# processor_board.net
KiCad netlist of a schematic drawn in EAGLE
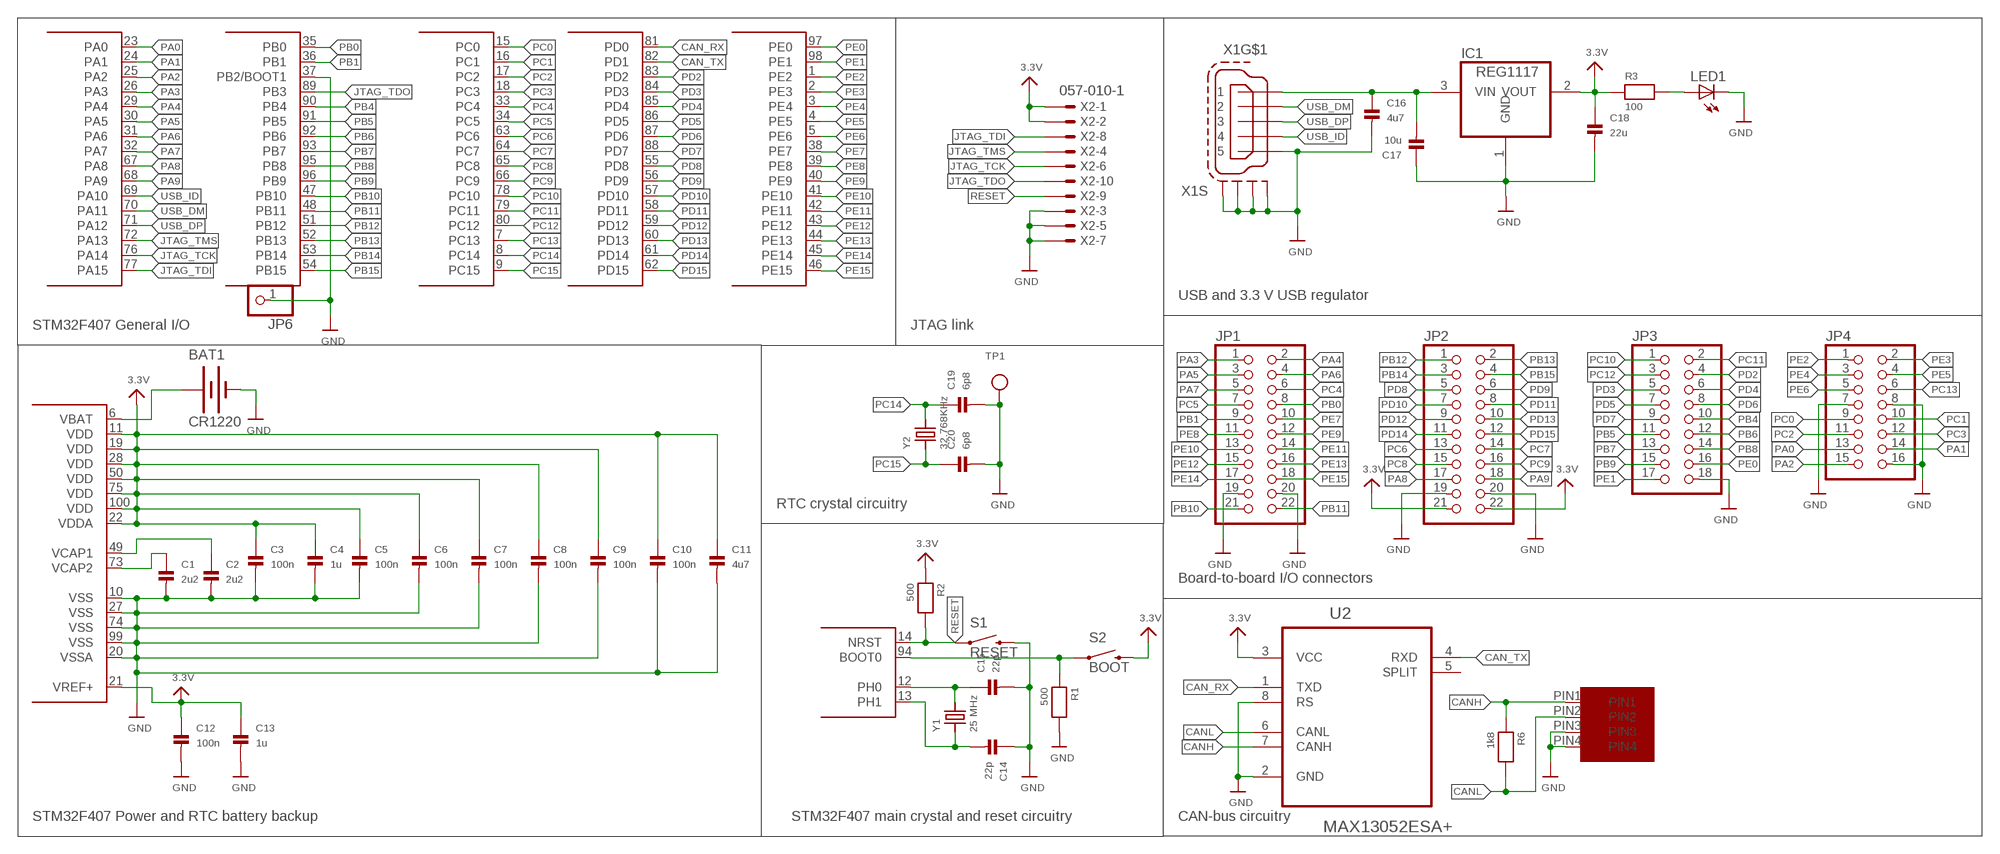
[diagram p0: schematic, sheet 1]

(export (version "E")
  (design (tool "Eeschema 10.0.6"))
  (components
    (comp (ref "BAT1")
      (value "CR1220")
      (footprint "eagle-import:BATTCON_12MM_PTH")
      (libsource (lib "eagle-import") (part "BATTERY12PTH"))
    )
    (comp (ref "C1")
      (value "2u2")
      (footprint "eagle-import:_0603MP")
      (libsource (lib "eagle-import") (part "CAP_CERAMIC_0603MP"))
    )
    (comp (ref "C2")
      (value "2u2")
      (footprint "eagle-import:_0603MP")
      (libsource (lib "eagle-import") (part "CAP_CERAMIC_0603MP"))
    )
    (comp (ref "C3")
      (value "100n")
      (footprint "eagle-import:_0603MP")
      (libsource (lib "eagle-import") (part "CAP_CERAMIC_0603MP"))
    )
    (comp (ref "C4")
      (value "1u")
      (footprint "eagle-import:_0603MP")
      (libsource (lib "eagle-import") (part "CAP_CERAMIC_0603MP"))
    )
    (comp (ref "C5")
      (value "100n")
      (footprint "eagle-import:_0603MP")
      (libsource (lib "eagle-import") (part "CAP_CERAMIC_0603MP"))
    )
    (comp (ref "C6")
      (value "100n")
      (footprint "eagle-import:_0603MP")
      (libsource (lib "eagle-import") (part "CAP_CERAMIC_0603MP"))
    )
    (comp (ref "C7")
      (value "100n")
      (footprint "eagle-import:_0603MP")
      (libsource (lib "eagle-import") (part "CAP_CERAMIC_0603MP"))
    )
    (comp (ref "C8")
      (value "100n")
      (footprint "eagle-import:_0603MP")
      (libsource (lib "eagle-import") (part "CAP_CERAMIC_0603MP"))
    )
    (comp (ref "C9")
      (value "100n")
      (footprint "eagle-import:_0603MP")
      (libsource (lib "eagle-import") (part "CAP_CERAMIC_0603MP"))
    )
    (comp (ref "C10")
      (value "100n")
      (footprint "eagle-import:_0603MP")
      (libsource (lib "eagle-import") (part "CAP_CERAMIC_0603MP"))
    )
    (comp (ref "C11")
      (value "4u7")
      (footprint "eagle-import:_0603MP")
      (libsource (lib "eagle-import") (part "CAP_CERAMIC_0603MP"))
    )
    (comp (ref "C12")
      (value "100n")
      (footprint "eagle-import:_0603MP")
      (libsource (lib "eagle-import") (part "CAP_CERAMIC_0603MP"))
    )
    (comp (ref "C13")
      (value "1u")
      (footprint "eagle-import:_0603MP")
      (libsource (lib "eagle-import") (part "CAP_CERAMIC_0603MP"))
    )
    (comp (ref "C14")
      (value "22p")
      (footprint "eagle-import:_0603MP")
      (libsource (lib "eagle-import") (part "CAP_CERAMIC_0603MP"))
    )
    (comp (ref "C15")
      (value "22p")
      (footprint "eagle-import:_0603MP")
      (libsource (lib "eagle-import") (part "CAP_CERAMIC_0603MP"))
    )
    (comp (ref "C16")
      (value "4u7")
      (footprint "eagle-import:_0603MP")
      (libsource (lib "eagle-import") (part "CAP_CERAMIC_0603MP"))
    )
    (comp (ref "C17")
      (value "10u")
      (footprint "eagle-import:_0603MP")
      (libsource (lib "eagle-import") (part "CAP_CERAMIC_0603MP"))
    )
    (comp (ref "C18")
      (value "22u")
      (footprint "eagle-import:_0603MP")
      (libsource (lib "eagle-import") (part "CAP_CERAMIC_0603MP"))
    )
    (comp (ref "C19")
      (value "6p8")
      (footprint "eagle-import:_0603MP")
      (libsource (lib "eagle-import") (part "CAP_CERAMIC_0603MP"))
    )
    (comp (ref "C20")
      (value "6p8")
      (footprint "eagle-import:_0603MP")
      (libsource (lib "eagle-import") (part "CAP_CERAMIC_0603MP"))
    )
    (comp (ref "IC1")
      (value "REG1117")
      (footprint "eagle-import:SOT223")
      (libsource (lib "eagle-import") (part "REG1117"))
    )
    (comp (ref "JP1")
      (value "PINHD-2X11")
      (footprint "eagle-import:2X11")
      (libsource (lib "eagle-import") (part "PINHD-2X11"))
    )
    (comp (ref "JP2")
      (value "PINHD-2X11")
      (footprint "eagle-import:2X11")
      (libsource (lib "eagle-import") (part "PINHD-2X11"))
    )
    (comp (ref "JP3")
      (value "PINHD-2X9")
      (footprint "eagle-import:2X09")
      (libsource (lib "eagle-import") (part "PINHD-2X9"))
    )
    (comp (ref "JP4")
      (value "PINHD-2X8")
      (footprint "eagle-import:2X08")
      (libsource (lib "eagle-import") (part "PINHD-2X8"))
    )
    (comp (ref "JP6")
      (value "PINHD-1X1")
      (footprint "eagle-import:1X01")
      (libsource (lib "eagle-import") (part "PINHD-1X1"))
    )
    (comp (ref "LED1")
      (value "LEDCHIPLED_1206")
      (footprint "eagle-import:CHIPLED_1206")
      (libsource (lib "eagle-import") (part "LEDCHIPLED_1206"))
    )
    (comp (ref "R1")
      (value "500")
      (footprint "eagle-import:_0603MP")
      (libsource (lib "eagle-import") (part "RESISTOR_0603MP"))
    )
    (comp (ref "R2")
      (value "500")
      (footprint "eagle-import:_0603MP")
      (libsource (lib "eagle-import") (part "RESISTOR_0603MP"))
    )
    (comp (ref "R3")
      (value "100")
      (footprint "eagle-import:_0603MP")
      (libsource (lib "eagle-import") (part "RESISTOR_0603MP"))
    )
    (comp (ref "R6")
      (value "1k8")
      (footprint "eagle-import:_0603MP")
      (libsource (lib "eagle-import") (part "RESISTOR_0603MP"))
    )
    (comp (ref "S1")
      (value "RESET")
      (footprint "eagle-import:TACTILE-SWITCH-1101NE")
      (libsource (lib "eagle-import") (part "SWITCH-MOMENTARY-2SMD-1101NE"))
    )
    (comp (ref "S2")
      (value "BOOT")
      (footprint "eagle-import:TACTILE-SWITCH-1101NE")
      (libsource (lib "eagle-import") (part "SWITCH-MOMENTARY-2SMD-1101NE"))
    )
    (comp (ref "TP1")
      (value "TESTPOINT0.1\"")
      (footprint "eagle-import:1X01_ROUND")
      (libsource (lib "eagle-import") (part "TESTPOINT0.1{dblquote}"))
    )
    (comp (ref "U$23")
      (value "MICROFIT4")
      (footprint "eagle-import:MICROFIT4SOCK")
      (libsource (lib "eagle-import") (part "MICROFIT4"))
    )
    (comp (ref "U1")
      (value "STM32F4-100")
      (footprint "eagle-import:SQFP-S-14X14-100")
      (libsource (lib "eagle-import") (part "STM32F4-100"))
    )
    (comp (ref "U2")
      (value "MAX13052ESA+")
      (footprint "eagle-import:SOIC127P600X175-8N")
      (libsource (lib "eagle-import") (part "MAX13052ESA+"))
    )
    (comp (ref "X1")
      (value "MINI-USB-SCHIELD-32005-201")
      (footprint "eagle-import:32005-201")
      (libsource (lib "eagle-import") (part "MINI-USB-SCHIELD-32005-201"))
    )
    (comp (ref "X2")
      (value "057-010-1")
      (footprint "eagle-import:057-010-1")
      (libsource (lib "eagle-import") (part "057-010-1"))
    )
    (comp (ref "Y1")
      (value "25 MHz")
      (footprint "eagle-import:CRYSTAL_2.5X2")
      (libsource (lib "eagle-import") (part "CRYSTAL2.5X2.0MM"))
    )
    (comp (ref "Y2")
      (value "32.768KHz")
      (footprint "eagle-import:CRYSTAL_CYL_2X6MM_SMT")
      (libsource (lib "eagle-import") (part "CRYSTAL32.768"))
    )
  )
  (nets
    (net (code "1") (name "3.3V") (class "Default")
      (node (ref "C10") (pin "1") (pinfunction "P$1_1") (pintype "passive"))
      (node (ref "C11") (pin "1") (pinfunction "P$1_1") (pintype "passive"))
      (node (ref "C12") (pin "1") (pinfunction "P$1_1") (pintype "passive"))
      (node (ref "C13") (pin "1") (pinfunction "P$1_1") (pintype "passive"))
      (node (ref "C18") (pin "1") (pinfunction "P$1_1") (pintype "passive"))
      (node (ref "C3") (pin "1") (pinfunction "P$1_1") (pintype "passive"))
      (node (ref "C4") (pin "1") (pinfunction "P$1_1") (pintype "passive"))
      (node (ref "C5") (pin "1") (pinfunction "P$1_1") (pintype "passive"))
      (node (ref "C6") (pin "1") (pinfunction "P$1_1") (pintype "passive"))
      (node (ref "C7") (pin "1") (pinfunction "P$1_1") (pintype "passive"))
      (node (ref "C8") (pin "1") (pinfunction "P$1_1") (pintype "passive"))
      (node (ref "C9") (pin "1") (pinfunction "P$1_1") (pintype "passive"))
      (node (ref "IC1") (pin "2") (pinfunction "VOUT_2") (pintype "output"))
      (node (ref "JP2") (pin "21") (pinfunction "21_21") (pintype "passive"))
      (node (ref "JP2") (pin "22") (pinfunction "22_22") (pintype "passive"))
      (node (ref "R2") (pin "1") (pinfunction "1_1") (pintype "passive"))
      (node (ref "R3") (pin "1") (pinfunction "1_1") (pintype "passive"))
      (node (ref "S2") (pin "2") (pinfunction "2_2") (pintype "passive"))
      (node (ref "U1") (pin "100") (pinfunction "VDD_100") (pintype "power_in"))
      (node (ref "U1") (pin "11") (pinfunction "VDD_11") (pintype "power_in"))
      (node (ref "U1") (pin "19") (pinfunction "VDD_19") (pintype "power_in"))
      (node (ref "U1") (pin "21") (pinfunction "VREF+_21") (pintype "passive"))
      (node (ref "U1") (pin "22") (pinfunction "VDDA_22") (pintype "power_in"))
      (node (ref "U1") (pin "28") (pinfunction "VDD_28") (pintype "power_in"))
      (node (ref "U1") (pin "50") (pinfunction "VDD_50") (pintype "power_in"))
      (node (ref "U1") (pin "75") (pinfunction "VDD_75") (pintype "power_in"))
      (node (ref "U2") (pin "3") (pinfunction "VCC_3") (pintype "power_in"))
      (node (ref "X2") (pin "1") (pinfunction "S_1") (pintype "passive"))
      (node (ref "X2") (pin "2") (pinfunction "S_2") (pintype "passive"))
    )
    (net (code "2") (name "CANH") (class "Default")
      (node (ref "R6") (pin "1") (pinfunction "1_1") (pintype "passive"))
      (node (ref "U$23") (pin "PIN1") (pinfunction "PIN1_PIN1") (pintype "bidirectional"))
      (node (ref "U2") (pin "7") (pinfunction "CANH_7") (pintype "input"))
    )
    (net (code "3") (name "CANL") (class "Default")
      (node (ref "R6") (pin "2") (pinfunction "2_2") (pintype "passive"))
      (node (ref "U$23") (pin "PIN2") (pinfunction "PIN2_PIN2") (pintype "bidirectional"))
      (node (ref "U2") (pin "6") (pinfunction "CANL_6") (pintype "input"))
    )
    (net (code "4") (name "CAN_RX") (class "Default")
      (node (ref "U1") (pin "81") (pinfunction "PD0_81") (pintype "bidirectional"))
      (node (ref "U2") (pin "1") (pinfunction "TXD_1") (pintype "input"))
    )
    (net (code "5") (name "CAN_TX") (class "Default")
      (node (ref "U1") (pin "82") (pinfunction "PD1_82") (pintype "bidirectional"))
      (node (ref "U2") (pin "4") (pinfunction "RXD_4") (pintype "output"))
    )
    (net (code "6") (name "GND") (class "Default")
      (node (ref "BAT1") (pin "GND") (pinfunction "-_GND") (pintype "power_in"))
      (node (ref "C1") (pin "2") (pinfunction "P$2_2") (pintype "passive"))
      (node (ref "C10") (pin "2") (pinfunction "P$2_2") (pintype "passive"))
      (node (ref "C11") (pin "2") (pinfunction "P$2_2") (pintype "passive"))
      (node (ref "C12") (pin "2") (pinfunction "P$2_2") (pintype "passive"))
      (node (ref "C13") (pin "2") (pinfunction "P$2_2") (pintype "passive"))
      (node (ref "C14") (pin "1") (pinfunction "P$1_1") (pintype "passive"))
      (node (ref "C15") (pin "2") (pinfunction "P$2_2") (pintype "passive"))
      (node (ref "C16") (pin "2") (pinfunction "P$2_2") (pintype "passive"))
      (node (ref "C17") (pin "1") (pinfunction "P$1_1") (pintype "passive"))
      (node (ref "C18") (pin "2") (pinfunction "P$2_2") (pintype "passive"))
      (node (ref "C19") (pin "2") (pinfunction "P$2_2") (pintype "passive"))
      (node (ref "C2") (pin "2") (pinfunction "P$2_2") (pintype "passive"))
      (node (ref "C20") (pin "2") (pinfunction "P$2_2") (pintype "passive"))
      (node (ref "C3") (pin "2") (pinfunction "P$2_2") (pintype "passive"))
      (node (ref "C4") (pin "2") (pinfunction "P$2_2") (pintype "passive"))
      (node (ref "C5") (pin "2") (pinfunction "P$2_2") (pintype "passive"))
      (node (ref "C6") (pin "2") (pinfunction "P$2_2") (pintype "passive"))
      (node (ref "C7") (pin "2") (pinfunction "P$2_2") (pintype "passive"))
      (node (ref "C8") (pin "2") (pinfunction "P$2_2") (pintype "passive"))
      (node (ref "C9") (pin "2") (pinfunction "P$2_2") (pintype "passive"))
      (node (ref "IC1") (pin "1") (pinfunction "GND_1") (pintype "power_in"))
      (node (ref "JP1") (pin "19") (pinfunction "19_19") (pintype "passive"))
      (node (ref "JP1") (pin "20") (pinfunction "20_20") (pintype "passive"))
      (node (ref "JP2") (pin "19") (pinfunction "19_19") (pintype "passive"))
      (node (ref "JP2") (pin "20") (pinfunction "20_20") (pintype "passive"))
      (node (ref "JP3") (pin "18") (pinfunction "18_18") (pintype "passive"))
      (node (ref "JP4") (pin "16") (pinfunction "16_16") (pintype "passive"))
      (node (ref "JP4") (pin "7") (pinfunction "7_7") (pintype "passive"))
      (node (ref "JP4") (pin "8") (pinfunction "8_8") (pintype "passive"))
      (node (ref "JP6") (pin "1") (pinfunction "1_1") (pintype "passive"))
      (node (ref "LED1") (pin "C") (pinfunction "C_C") (pintype "passive"))
      (node (ref "R1") (pin "2") (pinfunction "2_2") (pintype "passive"))
      (node (ref "S1") (pin "2") (pinfunction "2_2") (pintype "passive"))
      (node (ref "TP1") (pin "1") (pinfunction "P$1_1") (pintype "bidirectional"))
      (node (ref "U$23") (pin "PIN3") (pinfunction "PIN3_PIN3") (pintype "bidirectional"))
      (node (ref "U$23") (pin "PIN4") (pinfunction "PIN4_PIN4") (pintype "bidirectional"))
      (node (ref "U1") (pin "10") (pinfunction "VSS_10") (pintype "power_in"))
      (node (ref "U1") (pin "20") (pinfunction "VSSA_20") (pintype "power_in"))
      (node (ref "U1") (pin "27") (pinfunction "VSS_27") (pintype "power_in"))
      (node (ref "U1") (pin "37") (pinfunction "PB2/BOOT1_37") (pintype "bidirectional"))
      (node (ref "U1") (pin "74") (pinfunction "VSS_74") (pintype "power_in"))
      (node (ref "U1") (pin "99") (pinfunction "VSS_99") (pintype "power_in"))
      (node (ref "U2") (pin "2") (pinfunction "GND_2") (pintype "passive"))
      (node (ref "U2") (pin "8") (pinfunction "RS_8") (pintype "input"))
      (node (ref "X1") (pin "5") (pinfunction "5_5") (pintype "passive"))
      (node (ref "X1") (pin "M1") (pinfunction "S1_M1") (pintype "passive"))
      (node (ref "X1") (pin "M2") (pinfunction "S2_M2") (pintype "passive"))
      (node (ref "X1") (pin "M3") (pinfunction "S3_M3") (pintype "passive"))
      (node (ref "X1") (pin "M4") (pinfunction "S4_M4") (pintype "passive"))
      (node (ref "X2") (pin "3") (pinfunction "S_3") (pintype "passive"))
      (node (ref "X2") (pin "5") (pinfunction "S_5") (pintype "passive"))
      (node (ref "X2") (pin "7") (pinfunction "S_7") (pintype "passive"))
    )
    (net (code "7") (name "JTAG_TCK") (class "Default")
      (node (ref "U1") (pin "76") (pinfunction "PA14_76") (pintype "bidirectional"))
      (node (ref "X2") (pin "6") (pinfunction "S_6") (pintype "passive"))
    )
    (net (code "8") (name "JTAG_TDI") (class "Default")
      (node (ref "U1") (pin "77") (pinfunction "PA15_77") (pintype "bidirectional"))
      (node (ref "X2") (pin "8") (pinfunction "S_8") (pintype "passive"))
    )
    (net (code "9") (name "JTAG_TDO") (class "Default")
      (node (ref "U1") (pin "89") (pinfunction "PB3_89") (pintype "bidirectional"))
      (node (ref "X2") (pin "10") (pinfunction "S_10") (pintype "passive"))
    )
    (net (code "10") (name "JTAG_TMS") (class "Default")
      (node (ref "U1") (pin "72") (pinfunction "PA13_72") (pintype "bidirectional"))
      (node (ref "X2") (pin "4") (pinfunction "S_4") (pintype "passive"))
    )
    (net (code "11") (name "Net-(BAT1-+)") (class "Default")
      (node (ref "BAT1") (pin "VCC@1") (pinfunction "+_VCC@1") (pintype "power_in"))
      (node (ref "U1") (pin "6") (pinfunction "VBAT_6") (pintype "power_in"))
    )
    (net (code "12") (name "Net-(C1-P$1)") (class "Default")
      (node (ref "C1") (pin "1") (pinfunction "P$1_1") (pintype "passive"))
      (node (ref "U1") (pin "73") (pinfunction "VCAP2_73") (pintype "passive"))
    )
    (net (code "13") (name "Net-(C2-P$1)") (class "Default")
      (node (ref "C2") (pin "1") (pinfunction "P$1_1") (pintype "passive"))
      (node (ref "U1") (pin "49") (pinfunction "VCAP1_49") (pintype "passive"))
    )
    (net (code "14") (name "Net-(C14-P$2)") (class "Default")
      (node (ref "C14") (pin "2") (pinfunction "P$2_2") (pintype "passive"))
      (node (ref "U1") (pin "13") (pinfunction "PH1_13") (pintype "bidirectional"))
      (node (ref "Y1") (pin "1") (pinfunction "1_1") (pintype "passive"))
    )
    (net (code "15") (name "Net-(C15-P$1)") (class "Default")
      (node (ref "C15") (pin "1") (pinfunction "P$1_1") (pintype "passive"))
      (node (ref "U1") (pin "12") (pinfunction "PH0_12") (pintype "bidirectional"))
      (node (ref "Y1") (pin "3") (pinfunction "2_3") (pintype "passive"))
    )
    (net (code "16") (name "Net-(C16-P$1)") (class "Default")
      (node (ref "C16") (pin "1") (pinfunction "P$1_1") (pintype "passive"))
      (node (ref "C17") (pin "2") (pinfunction "P$2_2") (pintype "passive"))
      (node (ref "IC1") (pin "3") (pinfunction "VIN_3") (pintype "input"))
      (node (ref "X1") (pin "1") (pinfunction "1_1") (pintype "passive"))
    )
    (net (code "17") (name "Net-(LED1-PadA)") (class "Default")
      (node (ref "LED1") (pin "A") (pinfunction "A_A") (pintype "passive"))
      (node (ref "R3") (pin "2") (pinfunction "2_2") (pintype "passive"))
    )
    (net (code "18") (name "Net-(U1G-BOOT0)") (class "Default")
      (node (ref "R1") (pin "1") (pinfunction "1_1") (pintype "passive"))
      (node (ref "S2") (pin "1") (pinfunction "1_1") (pintype "passive"))
      (node (ref "U1") (pin "94") (pinfunction "BOOT0_94") (pintype "bidirectional"))
    )
    (net (code "19") (name "PA0") (class "Default")
      (node (ref "JP4") (pin "13") (pinfunction "13_13") (pintype "passive"))
      (node (ref "U1") (pin "23") (pinfunction "PA0_23") (pintype "bidirectional"))
    )
    (net (code "20") (name "PA1") (class "Default")
      (node (ref "JP4") (pin "14") (pinfunction "14_14") (pintype "passive"))
      (node (ref "U1") (pin "24") (pinfunction "PA1_24") (pintype "bidirectional"))
    )
    (net (code "21") (name "PA2") (class "Default")
      (node (ref "JP4") (pin "15") (pinfunction "15_15") (pintype "passive"))
      (node (ref "U1") (pin "25") (pinfunction "PA2_25") (pintype "bidirectional"))
    )
    (net (code "22") (name "PA3") (class "Default")
      (node (ref "JP1") (pin "1") (pinfunction "1_1") (pintype "passive"))
      (node (ref "U1") (pin "26") (pinfunction "PA3_26") (pintype "bidirectional"))
    )
    (net (code "23") (name "PA4") (class "Default")
      (node (ref "JP1") (pin "2") (pinfunction "2_2") (pintype "passive"))
      (node (ref "U1") (pin "29") (pinfunction "PA4_29") (pintype "bidirectional"))
    )
    (net (code "24") (name "PA5") (class "Default")
      (node (ref "JP1") (pin "3") (pinfunction "3_3") (pintype "passive"))
      (node (ref "U1") (pin "30") (pinfunction "PA5_30") (pintype "bidirectional"))
    )
    (net (code "25") (name "PA6") (class "Default")
      (node (ref "JP1") (pin "4") (pinfunction "4_4") (pintype "passive"))
      (node (ref "U1") (pin "31") (pinfunction "PA6_31") (pintype "bidirectional"))
    )
    (net (code "26") (name "PA7") (class "Default")
      (node (ref "JP1") (pin "5") (pinfunction "5_5") (pintype "passive"))
      (node (ref "U1") (pin "32") (pinfunction "PA7_32") (pintype "bidirectional"))
    )
    (net (code "27") (name "PA8") (class "Default")
      (node (ref "JP2") (pin "17") (pinfunction "17_17") (pintype "passive"))
      (node (ref "U1") (pin "67") (pinfunction "PA8_67") (pintype "bidirectional"))
    )
    (net (code "28") (name "PA9") (class "Default")
      (node (ref "JP2") (pin "18") (pinfunction "18_18") (pintype "passive"))
      (node (ref "U1") (pin "68") (pinfunction "PA9_68") (pintype "bidirectional"))
    )
    (net (code "29") (name "PB0") (class "Default")
      (node (ref "JP1") (pin "8") (pinfunction "8_8") (pintype "passive"))
      (node (ref "U1") (pin "35") (pinfunction "PB0_35") (pintype "bidirectional"))
    )
    (net (code "30") (name "PB1") (class "Default")
      (node (ref "JP1") (pin "9") (pinfunction "9_9") (pintype "passive"))
      (node (ref "U1") (pin "36") (pinfunction "PB1_36") (pintype "bidirectional"))
    )
    (net (code "31") (name "PB4") (class "Default")
      (node (ref "JP3") (pin "10") (pinfunction "10_10") (pintype "passive"))
      (node (ref "U1") (pin "90") (pinfunction "PB4_90") (pintype "bidirectional"))
    )
    (net (code "32") (name "PB5") (class "Default")
      (node (ref "JP3") (pin "11") (pinfunction "11_11") (pintype "passive"))
      (node (ref "U1") (pin "91") (pinfunction "PB5_91") (pintype "bidirectional"))
    )
    (net (code "33") (name "PB6") (class "Default")
      (node (ref "JP3") (pin "12") (pinfunction "12_12") (pintype "passive"))
      (node (ref "U1") (pin "92") (pinfunction "PB6_92") (pintype "bidirectional"))
    )
    (net (code "34") (name "PB7") (class "Default")
      (node (ref "JP3") (pin "13") (pinfunction "13_13") (pintype "passive"))
      (node (ref "U1") (pin "93") (pinfunction "PB7_93") (pintype "bidirectional"))
    )
    (net (code "35") (name "PB8") (class "Default")
      (node (ref "JP3") (pin "14") (pinfunction "14_14") (pintype "passive"))
      (node (ref "U1") (pin "95") (pinfunction "PB8_95") (pintype "bidirectional"))
    )
    (net (code "36") (name "PB9") (class "Default")
      (node (ref "JP3") (pin "15") (pinfunction "15_15") (pintype "passive"))
      (node (ref "U1") (pin "96") (pinfunction "PB9_96") (pintype "bidirectional"))
    )
    (net (code "37") (name "PB10") (class "Default")
      (node (ref "JP1") (pin "21") (pinfunction "21_21") (pintype "passive"))
      (node (ref "U1") (pin "47") (pinfunction "PB10_47") (pintype "bidirectional"))
    )
    (net (code "38") (name "PB11") (class "Default")
      (node (ref "JP1") (pin "22") (pinfunction "22_22") (pintype "passive"))
      (node (ref "U1") (pin "48") (pinfunction "PB11_48") (pintype "bidirectional"))
    )
    (net (code "39") (name "PB12") (class "Default")
      (node (ref "JP2") (pin "1") (pinfunction "1_1") (pintype "passive"))
      (node (ref "U1") (pin "51") (pinfunction "PB12_51") (pintype "bidirectional"))
    )
    (net (code "40") (name "PB13") (class "Default")
      (node (ref "JP2") (pin "2") (pinfunction "2_2") (pintype "passive"))
      (node (ref "U1") (pin "52") (pinfunction "PB13_52") (pintype "bidirectional"))
    )
    (net (code "41") (name "PB14") (class "Default")
      (node (ref "JP2") (pin "3") (pinfunction "3_3") (pintype "passive"))
      (node (ref "U1") (pin "53") (pinfunction "PB14_53") (pintype "bidirectional"))
    )
    (net (code "42") (name "PB15") (class "Default")
      (node (ref "JP2") (pin "4") (pinfunction "4_4") (pintype "passive"))
      (node (ref "U1") (pin "54") (pinfunction "PB15_54") (pintype "bidirectional"))
    )
    (net (code "43") (name "PC0") (class "Default")
      (node (ref "JP4") (pin "9") (pinfunction "9_9") (pintype "passive"))
      (node (ref "U1") (pin "15") (pinfunction "PC0_15") (pintype "bidirectional"))
    )
    (net (code "44") (name "PC1") (class "Default")
      (node (ref "JP4") (pin "10") (pinfunction "10_10") (pintype "passive"))
      (node (ref "U1") (pin "16") (pinfunction "PC1_16") (pintype "bidirectional"))
    )
    (net (code "45") (name "PC2") (class "Default")
      (node (ref "JP4") (pin "11") (pinfunction "11_11") (pintype "passive"))
      (node (ref "U1") (pin "17") (pinfunction "PC2_17") (pintype "bidirectional"))
    )
    (net (code "46") (name "PC3") (class "Default")
      (node (ref "JP4") (pin "12") (pinfunction "12_12") (pintype "passive"))
      (node (ref "U1") (pin "18") (pinfunction "PC3_18") (pintype "bidirectional"))
    )
    (net (code "47") (name "PC4") (class "Default")
      (node (ref "JP1") (pin "6") (pinfunction "6_6") (pintype "passive"))
      (node (ref "U1") (pin "33") (pinfunction "PC4_33") (pintype "bidirectional"))
    )
    (net (code "48") (name "PC5") (class "Default")
      (node (ref "JP1") (pin "7") (pinfunction "7_7") (pintype "passive"))
      (node (ref "U1") (pin "34") (pinfunction "PC5_34") (pintype "bidirectional"))
    )
    (net (code "49") (name "PC6") (class "Default")
      (node (ref "JP2") (pin "13") (pinfunction "13_13") (pintype "passive"))
      (node (ref "U1") (pin "63") (pinfunction "PC6_63") (pintype "bidirectional"))
    )
    (net (code "50") (name "PC7") (class "Default")
      (node (ref "JP2") (pin "14") (pinfunction "14_14") (pintype "passive"))
      (node (ref "U1") (pin "64") (pinfunction "PC7_64") (pintype "bidirectional"))
    )
    (net (code "51") (name "PC8") (class "Default")
      (node (ref "JP2") (pin "15") (pinfunction "15_15") (pintype "passive"))
      (node (ref "U1") (pin "65") (pinfunction "PC8_65") (pintype "bidirectional"))
    )
    (net (code "52") (name "PC9") (class "Default")
      (node (ref "JP2") (pin "16") (pinfunction "16_16") (pintype "passive"))
      (node (ref "U1") (pin "66") (pinfunction "PC9_66") (pintype "bidirectional"))
    )
    (net (code "53") (name "PC10") (class "Default")
      (node (ref "JP3") (pin "1") (pinfunction "1_1") (pintype "passive"))
      (node (ref "U1") (pin "78") (pinfunction "PC10_78") (pintype "bidirectional"))
    )
    (net (code "54") (name "PC11") (class "Default")
      (node (ref "JP3") (pin "2") (pinfunction "2_2") (pintype "passive"))
      (node (ref "U1") (pin "79") (pinfunction "PC11_79") (pintype "bidirectional"))
    )
    (net (code "55") (name "PC12") (class "Default")
      (node (ref "JP3") (pin "3") (pinfunction "3_3") (pintype "passive"))
      (node (ref "U1") (pin "80") (pinfunction "PC12_80") (pintype "bidirectional"))
    )
    (net (code "56") (name "PC13") (class "Default")
      (node (ref "JP4") (pin "6") (pinfunction "6_6") (pintype "passive"))
      (node (ref "U1") (pin "7") (pinfunction "PC13_7") (pintype "bidirectional"))
    )
    (net (code "57") (name "PC14") (class "Default")
      (node (ref "C19") (pin "1") (pinfunction "P$1_1") (pintype "passive"))
      (node (ref "U1") (pin "8") (pinfunction "PC14_8") (pintype "bidirectional"))
      (node (ref "Y2") (pin "2") (pinfunction "2_2") (pintype "passive"))
    )
    (net (code "58") (name "PC15") (class "Default")
      (node (ref "C20") (pin "1") (pinfunction "P$1_1") (pintype "passive"))
      (node (ref "U1") (pin "9") (pinfunction "PC15_9") (pintype "bidirectional"))
      (node (ref "Y2") (pin "1") (pinfunction "1_1") (pintype "passive"))
    )
    (net (code "59") (name "PD2") (class "Default")
      (node (ref "JP3") (pin "4") (pinfunction "4_4") (pintype "passive"))
      (node (ref "U1") (pin "83") (pinfunction "PD2_83") (pintype "bidirectional"))
    )
    (net (code "60") (name "PD3") (class "Default")
      (node (ref "JP3") (pin "5") (pinfunction "5_5") (pintype "passive"))
      (node (ref "U1") (pin "84") (pinfunction "PD3_84") (pintype "bidirectional"))
    )
    (net (code "61") (name "PD4") (class "Default")
      (node (ref "JP3") (pin "6") (pinfunction "6_6") (pintype "passive"))
      (node (ref "U1") (pin "85") (pinfunction "PD4_85") (pintype "bidirectional"))
    )
    (net (code "62") (name "PD5") (class "Default")
      (node (ref "JP3") (pin "7") (pinfunction "7_7") (pintype "passive"))
      (node (ref "U1") (pin "86") (pinfunction "PD5_86") (pintype "bidirectional"))
    )
    (net (code "63") (name "PD6") (class "Default")
      (node (ref "JP3") (pin "8") (pinfunction "8_8") (pintype "passive"))
      (node (ref "U1") (pin "87") (pinfunction "PD6_87") (pintype "bidirectional"))
    )
    (net (code "64") (name "PD7") (class "Default")
      (node (ref "JP3") (pin "9") (pinfunction "9_9") (pintype "passive"))
      (node (ref "U1") (pin "88") (pinfunction "PD7_88") (pintype "bidirectional"))
    )
    (net (code "65") (name "PD8") (class "Default")
      (node (ref "JP2") (pin "5") (pinfunction "5_5") (pintype "passive"))
      (node (ref "U1") (pin "55") (pinfunction "PD8_55") (pintype "bidirectional"))
    )
    (net (code "66") (name "PD9") (class "Default")
      (node (ref "JP2") (pin "6") (pinfunction "6_6") (pintype "passive"))
      (node (ref "U1") (pin "56") (pinfunction "PD9_56") (pintype "bidirectional"))
    )
    (net (code "67") (name "PD10") (class "Default")
      (node (ref "JP2") (pin "7") (pinfunction "7_7") (pintype "passive"))
      (node (ref "U1") (pin "57") (pinfunction "PD10_57") (pintype "bidirectional"))
    )
    (net (code "68") (name "PD11") (class "Default")
      (node (ref "JP2") (pin "8") (pinfunction "8_8") (pintype "passive"))
      (node (ref "U1") (pin "58") (pinfunction "PD11_58") (pintype "bidirectional"))
    )
    (net (code "69") (name "PD12") (class "Default")
      (node (ref "JP2") (pin "9") (pinfunction "9_9") (pintype "passive"))
      (node (ref "U1") (pin "59") (pinfunction "PD12_59") (pintype "bidirectional"))
    )
    (net (code "70") (name "PD13") (class "Default")
      (node (ref "JP2") (pin "10") (pinfunction "10_10") (pintype "passive"))
      (node (ref "U1") (pin "60") (pinfunction "PD13_60") (pintype "bidirectional"))
    )
    (net (code "71") (name "PD14") (class "Default")
      (node (ref "JP2") (pin "11") (pinfunction "11_11") (pintype "passive"))
      (node (ref "U1") (pin "61") (pinfunction "PD14_61") (pintype "bidirectional"))
    )
    (net (code "72") (name "PD15") (class "Default")
      (node (ref "JP2") (pin "12") (pinfunction "12_12") (pintype "passive"))
      (node (ref "U1") (pin "62") (pinfunction "PD15_62") (pintype "bidirectional"))
    )
    (net (code "73") (name "PE0") (class "Default")
      (node (ref "JP3") (pin "16") (pinfunction "16_16") (pintype "passive"))
      (node (ref "U1") (pin "97") (pinfunction "PE0_97") (pintype "bidirectional"))
    )
    (net (code "74") (name "PE1") (class "Default")
      (node (ref "JP3") (pin "17") (pinfunction "17_17") (pintype "passive"))
      (node (ref "U1") (pin "98") (pinfunction "PE1_98") (pintype "bidirectional"))
    )
    (net (code "75") (name "PE2") (class "Default")
      (node (ref "JP4") (pin "1") (pinfunction "1_1") (pintype "passive"))
      (node (ref "U1") (pin "1") (pinfunction "PE2_1") (pintype "bidirectional"))
    )
    (net (code "76") (name "PE3") (class "Default")
      (node (ref "JP4") (pin "2") (pinfunction "2_2") (pintype "passive"))
      (node (ref "U1") (pin "2") (pinfunction "PE3_2") (pintype "bidirectional"))
    )
    (net (code "77") (name "PE4") (class "Default")
      (node (ref "JP4") (pin "3") (pinfunction "3_3") (pintype "passive"))
      (node (ref "U1") (pin "3") (pinfunction "PE4_3") (pintype "bidirectional"))
    )
    (net (code "78") (name "PE5") (class "Default")
      (node (ref "JP4") (pin "4") (pinfunction "4_4") (pintype "passive"))
      (node (ref "U1") (pin "4") (pinfunction "PE5_4") (pintype "bidirectional"))
    )
    (net (code "79") (name "PE6") (class "Default")
      (node (ref "JP4") (pin "5") (pinfunction "5_5") (pintype "passive"))
      (node (ref "U1") (pin "5") (pinfunction "PE6_5") (pintype "bidirectional"))
    )
    (net (code "80") (name "PE7") (class "Default")
      (node (ref "JP1") (pin "10") (pinfunction "10_10") (pintype "passive"))
      (node (ref "U1") (pin "38") (pinfunction "PE7_38") (pintype "bidirectional"))
    )
    (net (code "81") (name "PE8") (class "Default")
      (node (ref "JP1") (pin "11") (pinfunction "11_11") (pintype "passive"))
      (node (ref "U1") (pin "39") (pinfunction "PE8_39") (pintype "bidirectional"))
    )
    (net (code "82") (name "PE9") (class "Default")
      (node (ref "JP1") (pin "12") (pinfunction "12_12") (pintype "passive"))
      (node (ref "U1") (pin "40") (pinfunction "PE9_40") (pintype "bidirectional"))
    )
    (net (code "83") (name "PE10") (class "Default")
      (node (ref "JP1") (pin "13") (pinfunction "13_13") (pintype "passive"))
      (node (ref "U1") (pin "41") (pinfunction "PE10_41") (pintype "bidirectional"))
    )
    (net (code "84") (name "PE11") (class "Default")
      (node (ref "JP1") (pin "14") (pinfunction "14_14") (pintype "passive"))
      (node (ref "U1") (pin "42") (pinfunction "PE11_42") (pintype "bidirectional"))
    )
    (net (code "85") (name "PE12") (class "Default")
      (node (ref "JP1") (pin "15") (pinfunction "15_15") (pintype "passive"))
      (node (ref "U1") (pin "43") (pinfunction "PE12_43") (pintype "bidirectional"))
    )
    (net (code "86") (name "PE13") (class "Default")
      (node (ref "JP1") (pin "16") (pinfunction "16_16") (pintype "passive"))
      (node (ref "U1") (pin "44") (pinfunction "PE13_44") (pintype "bidirectional"))
    )
    (net (code "87") (name "PE14") (class "Default")
      (node (ref "JP1") (pin "17") (pinfunction "17_17") (pintype "passive"))
      (node (ref "U1") (pin "45") (pinfunction "PE14_45") (pintype "bidirectional"))
    )
    (net (code "88") (name "PE15") (class "Default")
      (node (ref "JP1") (pin "18") (pinfunction "18_18") (pintype "passive"))
      (node (ref "U1") (pin "46") (pinfunction "PE15_46") (pintype "bidirectional"))
    )
    (net (code "89") (name "RESET") (class "Default")
      (node (ref "R2") (pin "2") (pinfunction "2_2") (pintype "passive"))
      (node (ref "S1") (pin "1") (pinfunction "1_1") (pintype "passive"))
      (node (ref "U1") (pin "14") (pinfunction "NRST_14") (pintype "bidirectional"))
      (node (ref "X2") (pin "9") (pinfunction "S_9") (pintype "passive"))
    )
    (net (code "90") (name "USB_DM") (class "Default")
      (node (ref "U1") (pin "70") (pinfunction "PA11_70") (pintype "bidirectional"))
      (node (ref "X1") (pin "2") (pinfunction "2_2") (pintype "passive"))
    )
    (net (code "91") (name "USB_DP") (class "Default")
      (node (ref "U1") (pin "71") (pinfunction "PA12_71") (pintype "bidirectional"))
      (node (ref "X1") (pin "3") (pinfunction "3_3") (pintype "passive"))
    )
    (net (code "92") (name "USB_ID") (class "Default")
      (node (ref "U1") (pin "69") (pinfunction "PA10_69") (pintype "bidirectional"))
      (node (ref "X1") (pin "4") (pinfunction "4_4") (pintype "passive"))
    )
    (net (code "93") (name "unconnected-(U2-SPLIT-Pad5)") (class "Default")
      (node (ref "U2") (pin "5") (pinfunction "SPLIT_5") (pintype "output"))
    )
  )
)
